# modulo_comunicacion_schdoc.net
KiCad netlist of a schematic drawn in Altium Designer
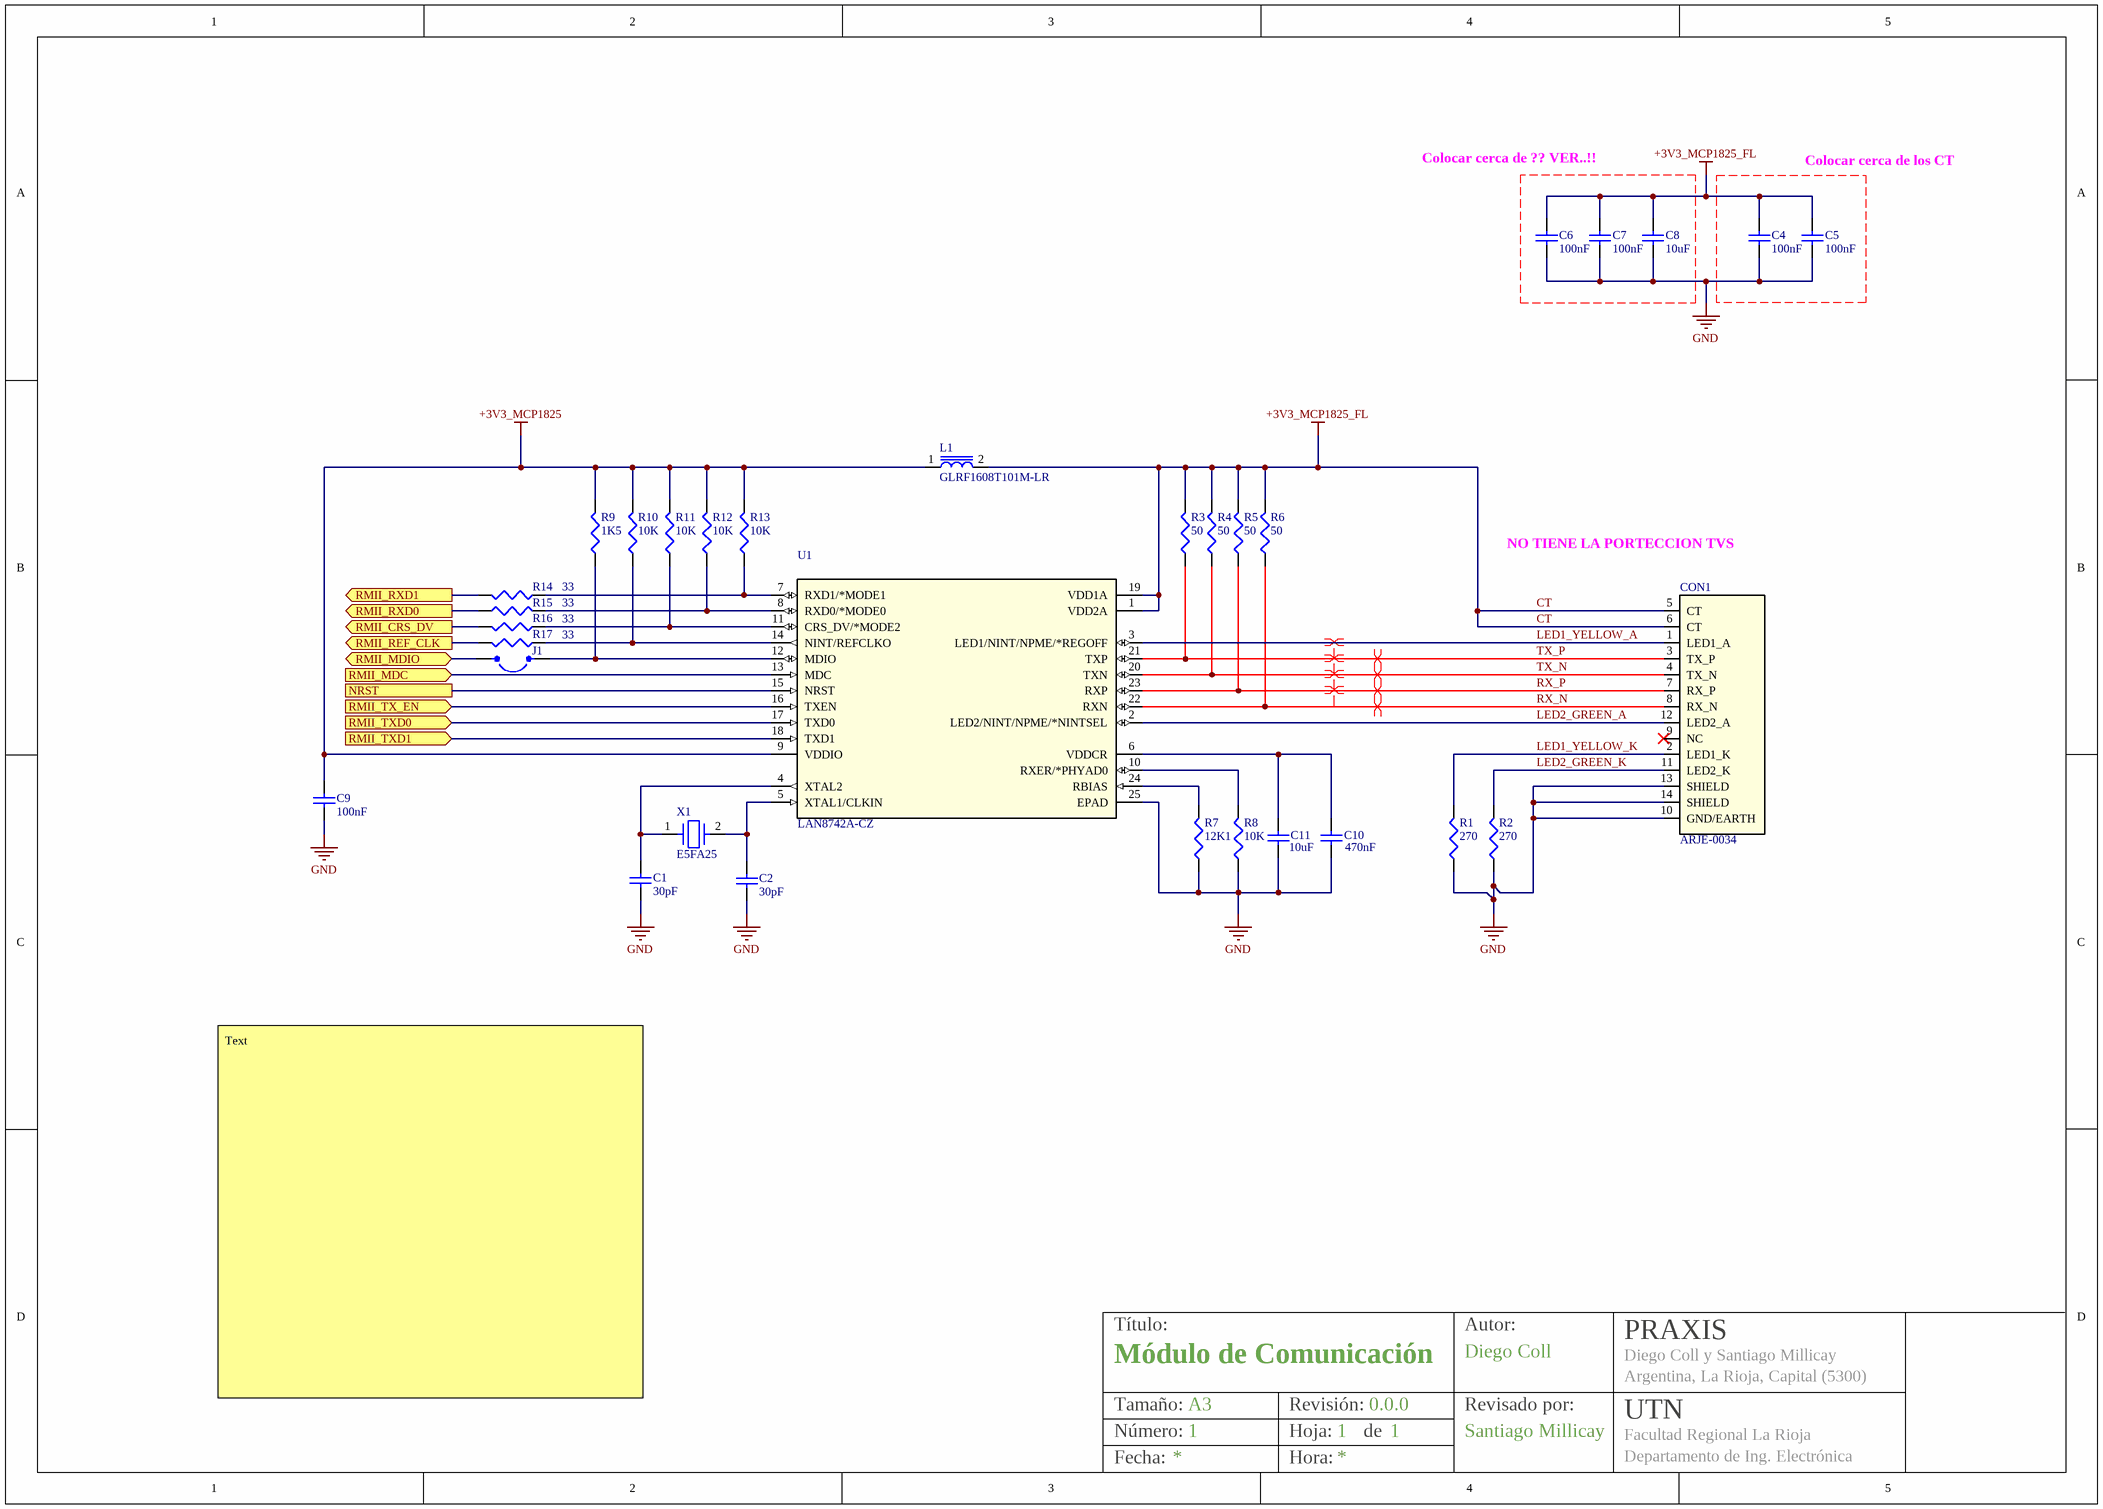
[diagram p0: modulo_comunicacion_schdoc.SchDoc]

(export (version "E")
  (design (tool "Eeschema 10.0.6"))
  (components
    (comp (ref "C1")
      (value "30pF")
      (footprint "1608[0603]")
      (description "Capacitor (Semiconductor SIM Model)")
      (fields (field (name "Comment") "Cap Semi") (field (name "PUBLISHER") "Altium Limited"))
      (libsource (lib "Miscellaneous Devices") (part "Cap Semi"))
    )
    (comp (ref "C2")
      (value "30pF")
      (footprint "1608[0603]")
      (description "Capacitor (Semiconductor SIM Model)")
      (fields (field (name "Comment") "Cap Semi") (field (name "PUBLISHER") "Altium Limited"))
      (libsource (lib "Miscellaneous Devices") (part "Cap Semi"))
    )
    (comp (ref "C4")
      (value "100nF")
      (footprint "1608[0603]")
      (description "Capacitor (Semiconductor SIM Model)")
      (fields (field (name "Comment") "Cap Semi") (field (name "PUBLISHER") "Altium Limited"))
      (libsource (lib "Miscellaneous Devices") (part "Cap Semi"))
    )
    (comp (ref "C5")
      (value "100nF")
      (footprint "1608[0603]")
      (description "Capacitor (Semiconductor SIM Model)")
      (fields (field (name "Comment") "Cap Semi") (field (name "PUBLISHER") "Altium Limited"))
      (libsource (lib "Miscellaneous Devices") (part "Cap Semi"))
    )
    (comp (ref "C6")
      (value "100nF")
      (footprint "1608[0603]")
      (description "Capacitor (Semiconductor SIM Model)")
      (fields (field (name "Comment") "Cap Semi") (field (name "PUBLISHER") "Altium Limited"))
      (libsource (lib "Miscellaneous Devices") (part "Cap Semi"))
    )
    (comp (ref "C7")
      (value "100nF")
      (footprint "1608[0603]")
      (description "Capacitor (Semiconductor SIM Model)")
      (fields (field (name "Comment") "Cap Semi") (field (name "PUBLISHER") "Altium Limited"))
      (libsource (lib "Miscellaneous Devices") (part "Cap Semi"))
    )
    (comp (ref "C8")
      (value "10uF")
      (footprint "1608[0603]")
      (description "Capacitor (Semiconductor SIM Model)")
      (fields (field (name "Comment") "Cap Semi") (field (name "PUBLISHER") "Altium Limited"))
      (libsource (lib "Miscellaneous Devices") (part "Cap Semi"))
    )
    (comp (ref "C9")
      (value "100nF")
      (footprint "1608[0603]")
      (description "Capacitor (Semiconductor SIM Model)")
      (fields (field (name "Comment") "Cap Semi") (field (name "PUBLISHER") "Altium Limited"))
      (libsource (lib "Miscellaneous Devices") (part "Cap Semi"))
    )
    (comp (ref "C10")
      (value "470nF")
      (footprint "C1206")
      (description "Capacitor (Semiconductor SIM Model)")
      (fields (field (name "Comment") "Cap Semi") (field (name "PUBLISHER") "Altium Limited"))
      (libsource (lib "Miscellaneous Devices") (part "Cap Semi"))
    )
    (comp (ref "C11")
      (value "10uF")
      (footprint "C1206")
      (description "Capacitor (Semiconductor SIM Model)")
      (fields (field (name "Comment") "Cap Semi") (field (name "PUBLISHER") "Altium Limited"))
      (libsource (lib "Miscellaneous Devices") (part "Cap Semi"))
    )
    (comp (ref "CON1")
      (value "ARJE-0034")
      (footprint "ARJE-0034")
      (description "CONECTOR RJ45 MAGNETICO")
      (fields (field (name "MANUFACTURER") "Abracon"))
      (libsource (lib "modulo_comunicacion_schlib") (part "ARJE-0034_MOD"))
    )
    (comp (ref "J1")
      (value "JUMPER_SMD_0603")
      (footprint "JUMPER_SMD_0603")
      (libsource (lib "modulo_comunicacion_schlib") (part "JUMPER_SMD_0603"))
    )
    (comp (ref "L1")
      (value "GLRF1608T101M-LR")
      (footprint "GLRF1608T101M-LR")
      (description "FIXED IND 100UH 80MA 5.5 OHM SMD")
      (fields
        (field (name "MANUFACTURER") "TDK")
        (field (name "MANUFACTURER PART NUMBER") "GLFR1608T101M-LR")
      )
      (libsource (lib "modulo_comunicacion_schlib") (part "GLRF1608T101M-LR"))
    )
    (comp (ref "R1")
      (value "270")
      (footprint "J1-0603")
      (description "Resistor")
      (fields (field (name "Comment") "Res3") (field (name "PUBLISHER") "Altium Limited"))
      (libsource (lib "Miscellaneous Devices") (part "Res3"))
    )
    (comp (ref "R2")
      (value "270")
      (footprint "J1-0603")
      (description "Resistor")
      (fields (field (name "Comment") "Res3") (field (name "PUBLISHER") "Altium Limited"))
      (libsource (lib "Miscellaneous Devices") (part "Res3"))
    )
    (comp (ref "R3")
      (value "50")
      (footprint "J1-0603")
      (description "Resistor")
      (fields (field (name "Comment") "Res3") (field (name "PUBLISHER") "Altium Limited"))
      (libsource (lib "Miscellaneous Devices") (part "Res3"))
    )
    (comp (ref "R4")
      (value "50")
      (footprint "J1-0603")
      (description "Resistor")
      (fields (field (name "Comment") "Res3") (field (name "PUBLISHER") "Altium Limited"))
      (libsource (lib "Miscellaneous Devices") (part "Res3"))
    )
    (comp (ref "R5")
      (value "50")
      (footprint "J1-0603")
      (description "Resistor")
      (fields (field (name "Comment") "Res3") (field (name "PUBLISHER") "Altium Limited"))
      (libsource (lib "Miscellaneous Devices") (part "Res3"))
    )
    (comp (ref "R6")
      (value "50")
      (footprint "J1-0603")
      (description "Resistor")
      (fields (field (name "Comment") "Res3") (field (name "PUBLISHER") "Altium Limited"))
      (libsource (lib "Miscellaneous Devices") (part "Res3"))
    )
    (comp (ref "R7")
      (value "12K1")
      (footprint "J1-0603")
      (description "Resistor")
      (fields (field (name "Comment") "Res3") (field (name "PUBLISHER") "Altium Limited"))
      (libsource (lib "Miscellaneous Devices") (part "Res3"))
    )
    (comp (ref "R8")
      (value "10K")
      (footprint "J1-0603")
      (description "Resistor")
      (fields (field (name "Comment") "Res3") (field (name "PUBLISHER") "Altium Limited"))
      (libsource (lib "Miscellaneous Devices") (part "Res3"))
    )
    (comp (ref "R9")
      (value "1K5")
      (footprint "J1-0603")
      (description "Resistor")
      (fields (field (name "Comment") "Res3") (field (name "PUBLISHER") "Altium Limited"))
      (libsource (lib "Miscellaneous Devices") (part "Res3"))
    )
    (comp (ref "R10")
      (value "10K")
      (footprint "J1-0603")
      (description "Resistor")
      (fields (field (name "Comment") "Res3") (field (name "PUBLISHER") "Altium Limited"))
      (libsource (lib "Miscellaneous Devices") (part "Res3"))
    )
    (comp (ref "R11")
      (value "10K")
      (footprint "J1-0603")
      (description "Resistor")
      (fields (field (name "Comment") "Res3") (field (name "PUBLISHER") "Altium Limited"))
      (libsource (lib "Miscellaneous Devices") (part "Res3"))
    )
    (comp (ref "R12")
      (value "10K")
      (footprint "J1-0603")
      (description "Resistor")
      (fields (field (name "Comment") "Res3") (field (name "PUBLISHER") "Altium Limited"))
      (libsource (lib "Miscellaneous Devices") (part "Res3"))
    )
    (comp (ref "R13")
      (value "10K")
      (footprint "J1-0603")
      (description "Resistor")
      (fields (field (name "Comment") "Res3") (field (name "PUBLISHER") "Altium Limited"))
      (libsource (lib "Miscellaneous Devices") (part "Res3"))
    )
    (comp (ref "R14")
      (value "33")
      (footprint "J1-0603")
      (description "Resistor")
      (fields (field (name "Comment") "Res3") (field (name "PUBLISHER") "Altium Limited"))
      (libsource (lib "Miscellaneous Devices") (part "Res3"))
    )
    (comp (ref "R15")
      (value "33")
      (footprint "J1-0603")
      (description "Resistor")
      (fields (field (name "Comment") "Res3") (field (name "PUBLISHER") "Altium Limited"))
      (libsource (lib "Miscellaneous Devices") (part "Res3"))
    )
    (comp (ref "R16")
      (value "33")
      (footprint "J1-0603")
      (description "Resistor")
      (fields (field (name "Comment") "Res3") (field (name "PUBLISHER") "Altium Limited"))
      (libsource (lib "Miscellaneous Devices") (part "Res3"))
    )
    (comp (ref "R17")
      (value "33")
      (footprint "J1-0603")
      (description "Resistor")
      (fields (field (name "Comment") "Res3") (field (name "PUBLISHER") "Altium Limited"))
      (libsource (lib "Miscellaneous Devices") (part "Res3"))
    )
    (comp (ref "U1")
      (value "LAN8742A-CZ")
      (footprint "LAN8742A-CZ")
      (description "IC TRANSCEIVER 1/1 24SQFN")
      (fields (field (name "MANUFACTURER") "Microchip"))
      (libsource (lib "modulo_comunicacion_schlib") (part "LAN8742A-CZ_MOD"))
    )
    (comp (ref "X1")
      (value "E5FA25")
      (footprint "E5FA25")
      (description "E5FA 25.0000 F15 E33")
      (libsource (lib "modulo_comunicacion_schlib") (part "E5FA25"))
    )
  )
  (nets
    (net (code "1") (name "+3V3_MCP1825") (class "Default")
      (node (ref "C9") (pin "2") (pinfunction "2_2") (pintype "passive"))
      (node (ref "L1") (pin "1") (pinfunction "1_1") (pintype "passive"))
      (node (ref "R10") (pin "2") (pinfunction "2_2") (pintype "passive"))
      (node (ref "R11") (pin "2") (pinfunction "2_2") (pintype "passive"))
      (node (ref "R12") (pin "2") (pinfunction "2_2") (pintype "passive"))
      (node (ref "R13") (pin "2") (pinfunction "2_2") (pintype "passive"))
      (node (ref "R9") (pin "2") (pinfunction "2_2") (pintype "passive"))
      (node (ref "U1") (pin "9") (pinfunction "VDDIO_9") (pintype "power_in"))
    )
    (net (code "2") (name "+3V3_MCP1825_FL") (class "Default")
      (node (ref "C4") (pin "2") (pinfunction "2_2") (pintype "passive"))
      (node (ref "C5") (pin "2") (pinfunction "2_2") (pintype "passive"))
      (node (ref "C6") (pin "2") (pinfunction "2_2") (pintype "passive"))
      (node (ref "C7") (pin "2") (pinfunction "2_2") (pintype "passive"))
      (node (ref "C8") (pin "2") (pinfunction "2_2") (pintype "passive"))
      (node (ref "CON1") (pin "5") (pinfunction "CT_5") (pintype "passive"))
      (node (ref "CON1") (pin "6") (pinfunction "CT_6") (pintype "passive"))
      (node (ref "L1") (pin "2") (pinfunction "2_2") (pintype "passive"))
      (node (ref "R3") (pin "2") (pinfunction "2_2") (pintype "passive"))
      (node (ref "R4") (pin "2") (pinfunction "2_2") (pintype "passive"))
      (node (ref "R5") (pin "2") (pinfunction "2_2") (pintype "passive"))
      (node (ref "R6") (pin "2") (pinfunction "2_2") (pintype "passive"))
      (node (ref "U1") (pin "1") (pinfunction "VDD2A_1") (pintype "power_in"))
      (node (ref "U1") (pin "19") (pinfunction "VDD1A_19") (pintype "power_in"))
    )
    (net (code "3") (name "/LED1_YELLOW_A") (class "Default")
      (node (ref "CON1") (pin "1") (pinfunction "LED1_A_1") (pintype "passive"))
      (node (ref "U1") (pin "3") (pinfunction "LED1/NINT/NPME/*REGOFF_3") (pintype "bidirectional"))
    )
    (net (code "4") (name "/LED1_YELLOW_K") (class "Default")
      (node (ref "CON1") (pin "2") (pinfunction "LED1_K_2") (pintype "passive"))
      (node (ref "R1") (pin "2") (pinfunction "2_2") (pintype "passive"))
    )
    (net (code "5") (name "/LED2_GREEN_A") (class "Default")
      (node (ref "CON1") (pin "12") (pinfunction "LED2_A_12") (pintype "passive"))
      (node (ref "U1") (pin "2") (pinfunction "LED2/NINT/NPME/*NINTSEL_2") (pintype "bidirectional"))
    )
    (net (code "6") (name "/LED2_GREEN_K") (class "Default")
      (node (ref "CON1") (pin "11") (pinfunction "LED2_K_11") (pintype "passive"))
      (node (ref "R2") (pin "2") (pinfunction "2_2") (pintype "passive"))
    )
    (net (code "7") (name "/NRST") (class "Default")
      (node (ref "U1") (pin "15") (pinfunction "NRST_15") (pintype "input"))
    )
    (net (code "8") (name "/RMII_CRS_DV") (class "Default")
      (node (ref "R16") (pin "2") (pinfunction "2_2") (pintype "passive"))
    )
    (net (code "9") (name "/RMII_MDC") (class "Default")
      (node (ref "U1") (pin "13") (pinfunction "MDC_13") (pintype "input"))
    )
    (net (code "10") (name "/RMII_MDIO") (class "Default")
      (node (ref "J1") (pin "1") (pinfunction "1_1") (pintype "passive"))
    )
    (net (code "11") (name "/RMII_REF_CLK") (class "Default")
      (node (ref "R17") (pin "2") (pinfunction "2_2") (pintype "passive"))
    )
    (net (code "12") (name "/RMII_RXD0") (class "Default")
      (node (ref "R15") (pin "1") (pinfunction "1_1") (pintype "passive"))
    )
    (net (code "13") (name "/RMII_RXD1") (class "Default")
      (node (ref "R14") (pin "2") (pinfunction "2_2") (pintype "passive"))
    )
    (net (code "14") (name "/RMII_TXD0") (class "Default")
      (node (ref "U1") (pin "17") (pinfunction "TXD0_17") (pintype "input"))
    )
    (net (code "15") (name "/RMII_TXD1") (class "Default")
      (node (ref "U1") (pin "18") (pinfunction "TXD1_18") (pintype "input"))
    )
    (net (code "16") (name "/RMII_TX_EN") (class "Default")
      (node (ref "U1") (pin "16") (pinfunction "TXEN_16") (pintype "input"))
    )
    (net (code "17") (name "/RX_N") (class "Default")
      (node (ref "CON1") (pin "8") (pinfunction "RX_N_8") (pintype "passive"))
      (node (ref "R6") (pin "1") (pinfunction "1_1") (pintype "passive"))
      (node (ref "U1") (pin "22") (pinfunction "RXN_22") (pintype "bidirectional"))
    )
    (net (code "18") (name "/RX_P") (class "Default")
      (node (ref "CON1") (pin "7") (pinfunction "RX_P_7") (pintype "passive"))
      (node (ref "R5") (pin "1") (pinfunction "1_1") (pintype "passive"))
      (node (ref "U1") (pin "23") (pinfunction "RXP_23") (pintype "bidirectional"))
    )
    (net (code "19") (name "/TX_N") (class "Default")
      (node (ref "CON1") (pin "4") (pinfunction "TX_N_4") (pintype "passive"))
      (node (ref "R4") (pin "1") (pinfunction "1_1") (pintype "passive"))
      (node (ref "U1") (pin "20") (pinfunction "TXN_20") (pintype "bidirectional"))
    )
    (net (code "20") (name "/TX_P") (class "Default")
      (node (ref "CON1") (pin "3") (pinfunction "TX_P_3") (pintype "passive"))
      (node (ref "R3") (pin "1") (pinfunction "1_1") (pintype "passive"))
      (node (ref "U1") (pin "21") (pinfunction "TXP_21") (pintype "bidirectional"))
    )
    (net (code "21") (name "GND") (class "Default")
      (node (ref "C1") (pin "1") (pinfunction "1_1") (pintype "passive"))
      (node (ref "C10") (pin "1") (pinfunction "1_1") (pintype "passive"))
      (node (ref "C11") (pin "1") (pinfunction "1_1") (pintype "passive"))
      (node (ref "C2") (pin "1") (pinfunction "1_1") (pintype "passive"))
      (node (ref "C4") (pin "1") (pinfunction "1_1") (pintype "passive"))
      (node (ref "C5") (pin "1") (pinfunction "1_1") (pintype "passive"))
      (node (ref "C6") (pin "1") (pinfunction "1_1") (pintype "passive"))
      (node (ref "C7") (pin "1") (pinfunction "1_1") (pintype "passive"))
      (node (ref "C8") (pin "1") (pinfunction "1_1") (pintype "passive"))
      (node (ref "C9") (pin "1") (pinfunction "1_1") (pintype "passive"))
      (node (ref "CON1") (pin "10") (pinfunction "GND/EARTH_10") (pintype "passive"))
      (node (ref "CON1") (pin "13") (pinfunction "SHIELD_13") (pintype "power_in"))
      (node (ref "CON1") (pin "14") (pinfunction "SHIELD_14") (pintype "power_in"))
      (node (ref "R1") (pin "1") (pinfunction "1_1") (pintype "passive"))
      (node (ref "R2") (pin "1") (pinfunction "1_1") (pintype "passive"))
      (node (ref "R7") (pin "1") (pinfunction "1_1") (pintype "passive"))
      (node (ref "R8") (pin "1") (pinfunction "1_1") (pintype "passive"))
      (node (ref "U1") (pin "25") (pinfunction "EPAD_25") (pintype "passive"))
    )
    (net (code "22") (name "Net-(U1-CRS_DV{slash}*MODE2)") (class "Default")
      (node (ref "R11") (pin "1") (pinfunction "1_1") (pintype "passive"))
      (node (ref "R16") (pin "1") (pinfunction "1_1") (pintype "passive"))
      (node (ref "U1") (pin "11") (pinfunction "CRS_DV/*MODE2_11") (pintype "bidirectional"))
    )
    (net (code "23") (name "Net-(U1-MDIO)") (class "Default")
      (node (ref "J1") (pin "2") (pinfunction "2_2") (pintype "passive"))
      (node (ref "R9") (pin "1") (pinfunction "1_1") (pintype "passive"))
      (node (ref "U1") (pin "12") (pinfunction "MDIO_12") (pintype "bidirectional"))
    )
    (net (code "24") (name "Net-(U1-NINT{slash}REFCLKO)") (class "Default")
      (node (ref "R10") (pin "1") (pinfunction "1_1") (pintype "passive"))
      (node (ref "R17") (pin "1") (pinfunction "1_1") (pintype "passive"))
      (node (ref "U1") (pin "14") (pinfunction "NINT/REFCLKO_14") (pintype "output"))
    )
    (net (code "25") (name "Net-(U1-RBIAS)") (class "Default")
      (node (ref "R7") (pin "2") (pinfunction "2_2") (pintype "passive"))
      (node (ref "U1") (pin "24") (pinfunction "RBIAS_24") (pintype "input"))
    )
    (net (code "26") (name "Net-(U1-RXD0{slash}*MODE0)") (class "Default")
      (node (ref "R12") (pin "1") (pinfunction "1_1") (pintype "passive"))
      (node (ref "R15") (pin "2") (pinfunction "2_2") (pintype "passive"))
      (node (ref "U1") (pin "8") (pinfunction "RXD0/*MODE0_8") (pintype "bidirectional"))
    )
    (net (code "27") (name "Net-(U1-RXD1{slash}*MODE1)") (class "Default")
      (node (ref "R13") (pin "1") (pinfunction "1_1") (pintype "passive"))
      (node (ref "R14") (pin "1") (pinfunction "1_1") (pintype "passive"))
      (node (ref "U1") (pin "7") (pinfunction "RXD1/*MODE1_7") (pintype "bidirectional"))
    )
    (net (code "28") (name "Net-(U1-RXER{slash}*PHYAD0)") (class "Default")
      (node (ref "R8") (pin "2") (pinfunction "2_2") (pintype "passive"))
      (node (ref "U1") (pin "10") (pinfunction "RXER/*PHYAD0_10") (pintype "bidirectional"))
    )
    (net (code "29") (name "Net-(U1-VDDCR)") (class "Default")
      (node (ref "C10") (pin "2") (pinfunction "2_2") (pintype "passive"))
      (node (ref "C11") (pin "2") (pinfunction "2_2") (pintype "passive"))
      (node (ref "U1") (pin "6") (pinfunction "VDDCR_6") (pintype "power_in"))
    )
    (net (code "30") (name "Net-(U1-XTAL1{slash}CLKIN)") (class "Default")
      (node (ref "C2") (pin "2") (pinfunction "2_2") (pintype "passive"))
      (node (ref "U1") (pin "5") (pinfunction "XTAL1/CLKIN_5") (pintype "input"))
      (node (ref "X1") (pin "2") (pinfunction "2_2") (pintype "passive"))
    )
    (net (code "31") (name "Net-(U1-XTAL2)") (class "Default")
      (node (ref "C1") (pin "2") (pinfunction "2_2") (pintype "passive"))
      (node (ref "U1") (pin "4") (pinfunction "XTAL2_4") (pintype "output"))
      (node (ref "X1") (pin "1") (pinfunction "1_1") (pintype "passive"))
    )
    (net (code "32") (name "unconnected-(CON1-NC-Pad9)") (class "Default")
      (node (ref "CON1") (pin "9") (pinfunction "NC_9") (pintype "passive+no_connect"))
    )
  )
)
